# rgbw2.net
KiCad netlist of a schematic drawn in EAGLE
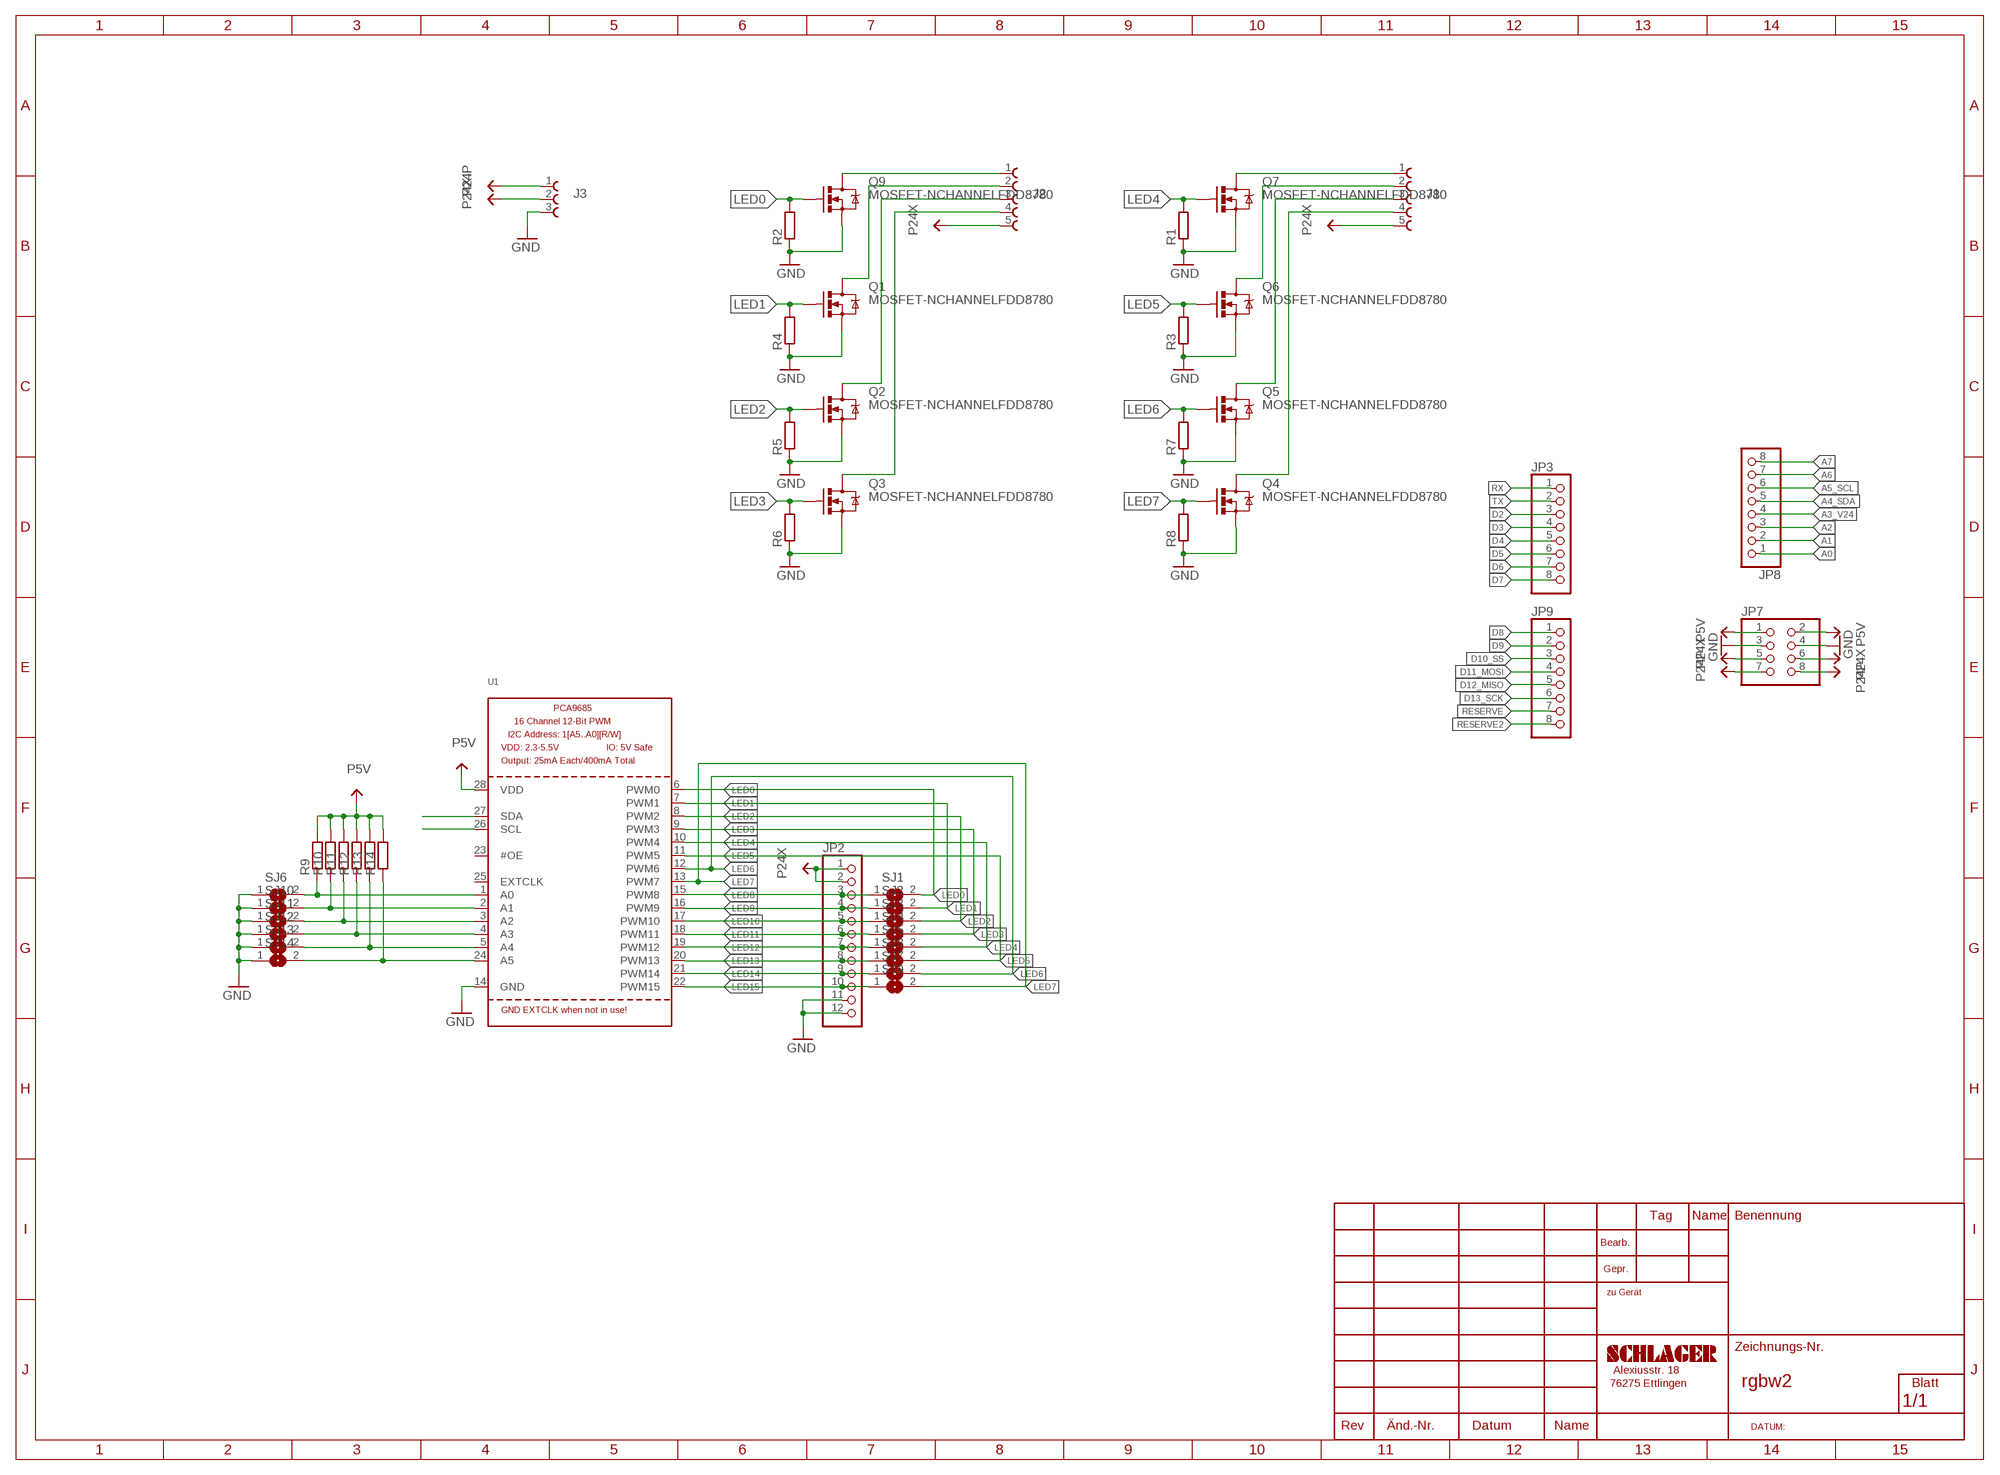
[diagram p0: schematic, sheet 1]

(export (version "E")
  (design (tool "Eeschema 10.0.6"))
  (components
    (comp (ref "J1")
      (value "691322310005")
      (footprint "eagle-import:691322310005")
      (libsource (lib "eagle-import") (part "691322310005"))
    )
    (comp (ref "J2")
      (value "691322310005")
      (footprint "eagle-import:691322310005")
      (libsource (lib "eagle-import") (part "691322310005"))
    )
    (comp (ref "J3")
      (value "691313510003")
      (footprint "eagle-import:691313510003")
      (libsource (lib "eagle-import") (part "691313510003"))
    )
    (comp (ref "JP2")
      (value "PINHD-1X12")
      (footprint "eagle-import:1X12")
      (libsource (lib "eagle-import") (part "PINHD-1X12"))
    )
    (comp (ref "JP3")
      (value "PINHD-1X8")
      (footprint "eagle-import:1X08")
      (libsource (lib "eagle-import") (part "PINHD-1X8"))
    )
    (comp (ref "JP7")
      (value "PINHD-2X4")
      (footprint "eagle-import:2X04")
      (libsource (lib "eagle-import") (part "PINHD-2X4"))
    )
    (comp (ref "JP8")
      (value "PINHD-1X8")
      (footprint "eagle-import:1X08")
      (libsource (lib "eagle-import") (part "PINHD-1X8"))
    )
    (comp (ref "JP9")
      (value "PINHD-1X8")
      (footprint "eagle-import:1X08")
      (libsource (lib "eagle-import") (part "PINHD-1X8"))
    )
    (comp (ref "Q1")
      (value "MOSFET-NCHANNELFDD8780")
      (footprint "eagle-import:DPAK")
      (libsource (lib "eagle-import") (part "MOSFET-NCHANNELFDD8780"))
    )
    (comp (ref "Q2")
      (value "MOSFET-NCHANNELFDD8780")
      (footprint "eagle-import:DPAK")
      (libsource (lib "eagle-import") (part "MOSFET-NCHANNELFDD8780"))
    )
    (comp (ref "Q3")
      (value "MOSFET-NCHANNELFDD8780")
      (footprint "eagle-import:DPAK")
      (libsource (lib "eagle-import") (part "MOSFET-NCHANNELFDD8780"))
    )
    (comp (ref "Q4")
      (value "MOSFET-NCHANNELFDD8780")
      (footprint "eagle-import:DPAK")
      (libsource (lib "eagle-import") (part "MOSFET-NCHANNELFDD8780"))
    )
    (comp (ref "Q5")
      (value "MOSFET-NCHANNELFDD8780")
      (footprint "eagle-import:DPAK")
      (libsource (lib "eagle-import") (part "MOSFET-NCHANNELFDD8780"))
    )
    (comp (ref "Q6")
      (value "MOSFET-NCHANNELFDD8780")
      (footprint "eagle-import:DPAK")
      (libsource (lib "eagle-import") (part "MOSFET-NCHANNELFDD8780"))
    )
    (comp (ref "Q7")
      (value "MOSFET-NCHANNELFDD8780")
      (footprint "eagle-import:DPAK")
      (libsource (lib "eagle-import") (part "MOSFET-NCHANNELFDD8780"))
    )
    (comp (ref "Q9")
      (value "MOSFET-NCHANNELFDD8780")
      (footprint "eagle-import:DPAK")
      (libsource (lib "eagle-import") (part "MOSFET-NCHANNELFDD8780"))
    )
    (comp (ref "R1")
      (value "R-EU_R0805")
      (footprint "eagle-import:R0805")
      (libsource (lib "eagle-import") (part "R-EU_R0805"))
    )
    (comp (ref "R2")
      (value "R-EU_R0805")
      (footprint "eagle-import:R0805")
      (libsource (lib "eagle-import") (part "R-EU_R0805"))
    )
    (comp (ref "R3")
      (value "R-EU_R0805")
      (footprint "eagle-import:R0805")
      (libsource (lib "eagle-import") (part "R-EU_R0805"))
    )
    (comp (ref "R4")
      (value "R-EU_R0805")
      (footprint "eagle-import:R0805")
      (libsource (lib "eagle-import") (part "R-EU_R0805"))
    )
    (comp (ref "R5")
      (value "R-EU_R0805")
      (footprint "eagle-import:R0805")
      (libsource (lib "eagle-import") (part "R-EU_R0805"))
    )
    (comp (ref "R6")
      (value "R-EU_R0805")
      (footprint "eagle-import:R0805")
      (libsource (lib "eagle-import") (part "R-EU_R0805"))
    )
    (comp (ref "R7")
      (value "R-EU_R0805")
      (footprint "eagle-import:R0805")
      (libsource (lib "eagle-import") (part "R-EU_R0805"))
    )
    (comp (ref "R8")
      (value "R-EU_R0805")
      (footprint "eagle-import:R0805")
      (libsource (lib "eagle-import") (part "R-EU_R0805"))
    )
    (comp (ref "R9")
      (value "R-EU_R0805")
      (footprint "eagle-import:R0805")
      (libsource (lib "eagle-import") (part "R-EU_R0805"))
    )
    (comp (ref "R10")
      (value "R-EU_R0805")
      (footprint "eagle-import:R0805")
      (libsource (lib "eagle-import") (part "R-EU_R0805"))
    )
    (comp (ref "R11")
      (value "R-EU_R0805")
      (footprint "eagle-import:R0805")
      (libsource (lib "eagle-import") (part "R-EU_R0805"))
    )
    (comp (ref "R12")
      (value "R-EU_R0805")
      (footprint "eagle-import:R0805")
      (libsource (lib "eagle-import") (part "R-EU_R0805"))
    )
    (comp (ref "R13")
      (value "R-EU_R0805")
      (footprint "eagle-import:R0805")
      (libsource (lib "eagle-import") (part "R-EU_R0805"))
    )
    (comp (ref "R14")
      (value "R-EU_R0805")
      (footprint "eagle-import:R0805")
      (libsource (lib "eagle-import") (part "R-EU_R0805"))
    )
    (comp (ref "SJ1")
      (value "SJN")
      (footprint "eagle-import:SJ")
      (libsource (lib "eagle-import") (part "SJN"))
    )
    (comp (ref "SJ2")
      (value "SJN")
      (footprint "eagle-import:SJ")
      (libsource (lib "eagle-import") (part "SJN"))
    )
    (comp (ref "SJ3")
      (value "SJN")
      (footprint "eagle-import:SJ")
      (libsource (lib "eagle-import") (part "SJN"))
    )
    (comp (ref "SJ4")
      (value "SJN")
      (footprint "eagle-import:SJ")
      (libsource (lib "eagle-import") (part "SJN"))
    )
    (comp (ref "SJ5")
      (value "SJN")
      (footprint "eagle-import:SJ")
      (libsource (lib "eagle-import") (part "SJN"))
    )
    (comp (ref "SJ6")
      (value "SJN")
      (footprint "eagle-import:SJ")
      (libsource (lib "eagle-import") (part "SJN"))
    )
    (comp (ref "SJ7")
      (value "SJN")
      (footprint "eagle-import:SJ")
      (libsource (lib "eagle-import") (part "SJN"))
    )
    (comp (ref "SJ8")
      (value "SJN")
      (footprint "eagle-import:SJ")
      (libsource (lib "eagle-import") (part "SJN"))
    )
    (comp (ref "SJ9")
      (value "SJN")
      (footprint "eagle-import:SJ")
      (libsource (lib "eagle-import") (part "SJN"))
    )
    (comp (ref "SJ10")
      (value "SJN")
      (footprint "eagle-import:SJ")
      (libsource (lib "eagle-import") (part "SJN"))
    )
    (comp (ref "SJ11")
      (value "SJN")
      (footprint "eagle-import:SJ")
      (libsource (lib "eagle-import") (part "SJN"))
    )
    (comp (ref "SJ12")
      (value "SJN")
      (footprint "eagle-import:SJ")
      (libsource (lib "eagle-import") (part "SJN"))
    )
    (comp (ref "SJ13")
      (value "SJN")
      (footprint "eagle-import:SJ")
      (libsource (lib "eagle-import") (part "SJN"))
    )
    (comp (ref "SJ14")
      (value "SJN")
      (footprint "eagle-import:SJ")
      (libsource (lib "eagle-import") (part "SJN"))
    )
    (comp (ref "U1")
      (value "PCA9685")
      (footprint "eagle-import:TSSOP28")
      (libsource (lib "eagle-import") (part "PCA9685"))
    )
  )
  (nets
    (net (code "1") (name "A0") (class "Default")
      (node (ref "JP8") (pin "1") (pinfunction "1_1") (pintype "passive"))
    )
    (net (code "2") (name "A1") (class "Default")
      (node (ref "JP8") (pin "2") (pinfunction "2_2") (pintype "passive"))
    )
    (net (code "3") (name "A2") (class "Default")
      (node (ref "JP8") (pin "3") (pinfunction "3_3") (pintype "passive"))
    )
    (net (code "4") (name "A3_V24") (class "Default")
      (node (ref "JP8") (pin "4") (pinfunction "4_4") (pintype "passive"))
    )
    (net (code "5") (name "A4_SDA") (class "Default")
      (node (ref "JP8") (pin "5") (pinfunction "5_5") (pintype "passive"))
      (node (ref "U1") (pin "27") (pinfunction "SDA_27") (pintype "bidirectional"))
    )
    (net (code "6") (name "A5_SCL") (class "Default")
      (node (ref "JP8") (pin "6") (pinfunction "6_6") (pintype "passive"))
      (node (ref "U1") (pin "26") (pinfunction "SCL_26") (pintype "bidirectional"))
    )
    (net (code "7") (name "A6") (class "Default")
      (node (ref "JP8") (pin "7") (pinfunction "7_7") (pintype "passive"))
    )
    (net (code "8") (name "A7") (class "Default")
      (node (ref "JP8") (pin "8") (pinfunction "8_8") (pintype "passive"))
    )
    (net (code "9") (name "D2") (class "Default")
      (node (ref "JP3") (pin "3") (pinfunction "3_3") (pintype "passive"))
    )
    (net (code "10") (name "D3") (class "Default")
      (node (ref "JP3") (pin "4") (pinfunction "4_4") (pintype "passive"))
    )
    (net (code "11") (name "D4") (class "Default")
      (node (ref "JP3") (pin "5") (pinfunction "5_5") (pintype "passive"))
    )
    (net (code "12") (name "D5") (class "Default")
      (node (ref "JP3") (pin "6") (pinfunction "6_6") (pintype "passive"))
    )
    (net (code "13") (name "D6") (class "Default")
      (node (ref "JP3") (pin "7") (pinfunction "7_7") (pintype "passive"))
    )
    (net (code "14") (name "D7") (class "Default")
      (node (ref "JP3") (pin "8") (pinfunction "8_8") (pintype "passive"))
    )
    (net (code "15") (name "D8") (class "Default")
      (node (ref "JP9") (pin "1") (pinfunction "1_1") (pintype "passive"))
    )
    (net (code "16") (name "D9") (class "Default")
      (node (ref "JP9") (pin "2") (pinfunction "2_2") (pintype "passive"))
    )
    (net (code "17") (name "D10_SS") (class "Default")
      (node (ref "JP9") (pin "3") (pinfunction "3_3") (pintype "passive"))
    )
    (net (code "18") (name "D11_MOSI") (class "Default")
      (node (ref "JP9") (pin "4") (pinfunction "4_4") (pintype "passive"))
    )
    (net (code "19") (name "D12_MISO") (class "Default")
      (node (ref "JP9") (pin "5") (pinfunction "5_5") (pintype "passive"))
    )
    (net (code "20") (name "D13_SCK") (class "Default")
      (node (ref "JP9") (pin "6") (pinfunction "6_6") (pintype "passive"))
    )
    (net (code "21") (name "GND") (class "Default")
      (node (ref "J3") (pin "3") (pinfunction "3_3") (pintype "passive"))
      (node (ref "JP2") (pin "11") (pinfunction "11_11") (pintype "passive"))
      (node (ref "JP2") (pin "12") (pinfunction "12_12") (pintype "passive"))
      (node (ref "JP7") (pin "3") (pinfunction "3_3") (pintype "passive"))
      (node (ref "JP7") (pin "4") (pinfunction "4_4") (pintype "passive"))
      (node (ref "Q1") (pin "3") (pinfunction "S_3") (pintype "passive"))
      (node (ref "Q2") (pin "3") (pinfunction "S_3") (pintype "passive"))
      (node (ref "Q3") (pin "3") (pinfunction "S_3") (pintype "passive"))
      (node (ref "Q4") (pin "3") (pinfunction "S_3") (pintype "passive"))
      (node (ref "Q5") (pin "3") (pinfunction "S_3") (pintype "passive"))
      (node (ref "Q6") (pin "3") (pinfunction "S_3") (pintype "passive"))
      (node (ref "Q7") (pin "3") (pinfunction "S_3") (pintype "passive"))
      (node (ref "Q9") (pin "3") (pinfunction "S_3") (pintype "passive"))
      (node (ref "R1") (pin "1") (pinfunction "1_1") (pintype "passive"))
      (node (ref "R2") (pin "1") (pinfunction "1_1") (pintype "passive"))
      (node (ref "R3") (pin "1") (pinfunction "1_1") (pintype "passive"))
      (node (ref "R4") (pin "1") (pinfunction "1_1") (pintype "passive"))
      (node (ref "R5") (pin "1") (pinfunction "1_1") (pintype "passive"))
      (node (ref "R6") (pin "1") (pinfunction "1_1") (pintype "passive"))
      (node (ref "R7") (pin "1") (pinfunction "1_1") (pintype "passive"))
      (node (ref "R8") (pin "1") (pinfunction "1_1") (pintype "passive"))
      (node (ref "SJ10") (pin "1") (pinfunction "1_1") (pintype "passive"))
      (node (ref "SJ11") (pin "1") (pinfunction "1_1") (pintype "passive"))
      (node (ref "SJ12") (pin "1") (pinfunction "1_1") (pintype "passive"))
      (node (ref "SJ13") (pin "1") (pinfunction "1_1") (pintype "passive"))
      (node (ref "SJ14") (pin "1") (pinfunction "1_1") (pintype "passive"))
      (node (ref "SJ6") (pin "1") (pinfunction "1_1") (pintype "passive"))
      (node (ref "U1") (pin "14") (pinfunction "GND_14") (pintype "power_in"))
    )
    (net (code "22") (name "LED0") (class "Default")
      (node (ref "Q9") (pin "1") (pinfunction "G_1") (pintype "passive"))
      (node (ref "R2") (pin "2") (pinfunction "2_2") (pintype "passive"))
      (node (ref "SJ1") (pin "2") (pinfunction "2_2") (pintype "passive"))
      (node (ref "U1") (pin "6") (pinfunction "PWM0_6") (pintype "output"))
    )
    (net (code "23") (name "LED1") (class "Default")
      (node (ref "Q1") (pin "1") (pinfunction "G_1") (pintype "passive"))
      (node (ref "R4") (pin "2") (pinfunction "2_2") (pintype "passive"))
      (node (ref "SJ2") (pin "2") (pinfunction "2_2") (pintype "passive"))
      (node (ref "U1") (pin "7") (pinfunction "PWM1_7") (pintype "output"))
    )
    (net (code "24") (name "LED2") (class "Default")
      (node (ref "Q2") (pin "1") (pinfunction "G_1") (pintype "passive"))
      (node (ref "R5") (pin "2") (pinfunction "2_2") (pintype "passive"))
      (node (ref "SJ3") (pin "2") (pinfunction "2_2") (pintype "passive"))
      (node (ref "U1") (pin "8") (pinfunction "PWM2_8") (pintype "output"))
    )
    (net (code "25") (name "LED3") (class "Default")
      (node (ref "Q3") (pin "1") (pinfunction "G_1") (pintype "passive"))
      (node (ref "R6") (pin "2") (pinfunction "2_2") (pintype "passive"))
      (node (ref "SJ4") (pin "2") (pinfunction "2_2") (pintype "passive"))
      (node (ref "U1") (pin "9") (pinfunction "PWM3_9") (pintype "output"))
    )
    (net (code "26") (name "LED4") (class "Default")
      (node (ref "Q7") (pin "1") (pinfunction "G_1") (pintype "passive"))
      (node (ref "R1") (pin "2") (pinfunction "2_2") (pintype "passive"))
      (node (ref "SJ5") (pin "2") (pinfunction "2_2") (pintype "passive"))
      (node (ref "U1") (pin "10") (pinfunction "PWM4_10") (pintype "output"))
    )
    (net (code "27") (name "LED5") (class "Default")
      (node (ref "Q6") (pin "1") (pinfunction "G_1") (pintype "passive"))
      (node (ref "R3") (pin "2") (pinfunction "2_2") (pintype "passive"))
      (node (ref "SJ8") (pin "2") (pinfunction "2_2") (pintype "passive"))
      (node (ref "U1") (pin "11") (pinfunction "PWM5_11") (pintype "output"))
    )
    (net (code "28") (name "LED6") (class "Default")
      (node (ref "Q5") (pin "1") (pinfunction "G_1") (pintype "passive"))
      (node (ref "R7") (pin "2") (pinfunction "2_2") (pintype "passive"))
      (node (ref "SJ7") (pin "2") (pinfunction "2_2") (pintype "passive"))
      (node (ref "U1") (pin "12") (pinfunction "PWM6_12") (pintype "output"))
    )
    (net (code "29") (name "LED7") (class "Default")
      (node (ref "Q4") (pin "1") (pinfunction "G_1") (pintype "passive"))
      (node (ref "R8") (pin "2") (pinfunction "2_2") (pintype "passive"))
      (node (ref "SJ9") (pin "2") (pinfunction "2_2") (pintype "passive"))
      (node (ref "U1") (pin "13") (pinfunction "PWM7_13") (pintype "output"))
    )
    (net (code "30") (name "LED8") (class "Default")
      (node (ref "JP2") (pin "3") (pinfunction "3_3") (pintype "passive"))
      (node (ref "SJ1") (pin "1") (pinfunction "1_1") (pintype "passive"))
      (node (ref "U1") (pin "15") (pinfunction "PWM8_15") (pintype "output"))
    )
    (net (code "31") (name "LED9") (class "Default")
      (node (ref "JP2") (pin "4") (pinfunction "4_4") (pintype "passive"))
      (node (ref "SJ2") (pin "1") (pinfunction "1_1") (pintype "passive"))
      (node (ref "U1") (pin "16") (pinfunction "PWM9_16") (pintype "output"))
    )
    (net (code "32") (name "LED10") (class "Default")
      (node (ref "JP2") (pin "5") (pinfunction "5_5") (pintype "passive"))
      (node (ref "SJ3") (pin "1") (pinfunction "1_1") (pintype "passive"))
      (node (ref "U1") (pin "17") (pinfunction "PWM10_17") (pintype "output"))
    )
    (net (code "33") (name "LED11") (class "Default")
      (node (ref "JP2") (pin "6") (pinfunction "6_6") (pintype "passive"))
      (node (ref "SJ4") (pin "1") (pinfunction "1_1") (pintype "passive"))
      (node (ref "U1") (pin "18") (pinfunction "PWM11_18") (pintype "output"))
    )
    (net (code "34") (name "LED12") (class "Default")
      (node (ref "JP2") (pin "7") (pinfunction "7_7") (pintype "passive"))
      (node (ref "SJ5") (pin "1") (pinfunction "1_1") (pintype "passive"))
      (node (ref "U1") (pin "19") (pinfunction "PWM12_19") (pintype "output"))
    )
    (net (code "35") (name "LED13") (class "Default")
      (node (ref "JP2") (pin "8") (pinfunction "8_8") (pintype "passive"))
      (node (ref "SJ8") (pin "1") (pinfunction "1_1") (pintype "passive"))
      (node (ref "U1") (pin "20") (pinfunction "PWM13_20") (pintype "output"))
    )
    (net (code "36") (name "LED14") (class "Default")
      (node (ref "JP2") (pin "9") (pinfunction "9_9") (pintype "passive"))
      (node (ref "SJ7") (pin "1") (pinfunction "1_1") (pintype "passive"))
      (node (ref "U1") (pin "21") (pinfunction "PWM14_21") (pintype "output"))
    )
    (net (code "37") (name "LED15") (class "Default")
      (node (ref "JP2") (pin "10") (pinfunction "10_10") (pintype "passive"))
      (node (ref "SJ9") (pin "1") (pinfunction "1_1") (pintype "passive"))
      (node (ref "U1") (pin "22") (pinfunction "PWM15_22") (pintype "output"))
    )
    (net (code "38") (name "Net-(Q1-D)") (class "Default")
      (node (ref "J2") (pin "2") (pinfunction "2_2") (pintype "passive"))
      (node (ref "Q1") (pin "4") (pinfunction "D_4") (pintype "passive"))
    )
    (net (code "39") (name "Net-(Q2-D)") (class "Default")
      (node (ref "J2") (pin "3") (pinfunction "3_3") (pintype "passive"))
      (node (ref "Q2") (pin "4") (pinfunction "D_4") (pintype "passive"))
    )
    (net (code "40") (name "Net-(Q3-D)") (class "Default")
      (node (ref "J2") (pin "4") (pinfunction "4_4") (pintype "passive"))
      (node (ref "Q3") (pin "4") (pinfunction "D_4") (pintype "passive"))
    )
    (net (code "41") (name "Net-(Q4-D)") (class "Default")
      (node (ref "J1") (pin "4") (pinfunction "4_4") (pintype "passive"))
      (node (ref "Q4") (pin "4") (pinfunction "D_4") (pintype "passive"))
    )
    (net (code "42") (name "Net-(Q5-D)") (class "Default")
      (node (ref "J1") (pin "3") (pinfunction "3_3") (pintype "passive"))
      (node (ref "Q5") (pin "4") (pinfunction "D_4") (pintype "passive"))
    )
    (net (code "43") (name "Net-(Q6-D)") (class "Default")
      (node (ref "J1") (pin "2") (pinfunction "2_2") (pintype "passive"))
      (node (ref "Q6") (pin "4") (pinfunction "D_4") (pintype "passive"))
    )
    (net (code "44") (name "Net-(Q7-D)") (class "Default")
      (node (ref "J1") (pin "1") (pinfunction "1_1") (pintype "passive"))
      (node (ref "Q7") (pin "4") (pinfunction "D_4") (pintype "passive"))
    )
    (net (code "45") (name "Net-(Q9-D)") (class "Default")
      (node (ref "J2") (pin "1") (pinfunction "1_1") (pintype "passive"))
      (node (ref "Q9") (pin "4") (pinfunction "D_4") (pintype "passive"))
    )
    (net (code "46") (name "Net-(U1-A0)") (class "Default")
      (node (ref "R9") (pin "1") (pinfunction "1_1") (pintype "passive"))
      (node (ref "SJ6") (pin "2") (pinfunction "2_2") (pintype "passive"))
      (node (ref "U1") (pin "1") (pinfunction "A0_1") (pintype "bidirectional"))
    )
    (net (code "47") (name "Net-(U1-A1)") (class "Default")
      (node (ref "R10") (pin "1") (pinfunction "1_1") (pintype "passive"))
      (node (ref "SJ10") (pin "2") (pinfunction "2_2") (pintype "passive"))
      (node (ref "U1") (pin "2") (pinfunction "A1_2") (pintype "bidirectional"))
    )
    (net (code "48") (name "Net-(U1-A2)") (class "Default")
      (node (ref "R11") (pin "1") (pinfunction "1_1") (pintype "passive"))
      (node (ref "SJ11") (pin "2") (pinfunction "2_2") (pintype "passive"))
      (node (ref "U1") (pin "3") (pinfunction "A2_3") (pintype "bidirectional"))
    )
    (net (code "49") (name "Net-(U1-A3)") (class "Default")
      (node (ref "R12") (pin "1") (pinfunction "1_1") (pintype "passive"))
      (node (ref "SJ12") (pin "2") (pinfunction "2_2") (pintype "passive"))
      (node (ref "U1") (pin "4") (pinfunction "A3_4") (pintype "bidirectional"))
    )
    (net (code "50") (name "Net-(U1-A4)") (class "Default")
      (node (ref "R13") (pin "1") (pinfunction "1_1") (pintype "passive"))
      (node (ref "SJ13") (pin "2") (pinfunction "2_2") (pintype "passive"))
      (node (ref "U1") (pin "5") (pinfunction "A4_5") (pintype "bidirectional"))
    )
    (net (code "51") (name "Net-(U1-A5)") (class "Default")
      (node (ref "R14") (pin "1") (pinfunction "1_1") (pintype "passive"))
      (node (ref "SJ14") (pin "2") (pinfunction "2_2") (pintype "passive"))
      (node (ref "U1") (pin "24") (pinfunction "A5_24") (pintype "bidirectional"))
    )
    (net (code "52") (name "P5V") (class "Default")
      (node (ref "JP7") (pin "1") (pinfunction "1_1") (pintype "passive"))
      (node (ref "JP7") (pin "2") (pinfunction "2_2") (pintype "passive"))
      (node (ref "R10") (pin "2") (pinfunction "2_2") (pintype "passive"))
      (node (ref "R11") (pin "2") (pinfunction "2_2") (pintype "passive"))
      (node (ref "R12") (pin "2") (pinfunction "2_2") (pintype "passive"))
      (node (ref "R13") (pin "2") (pinfunction "2_2") (pintype "passive"))
      (node (ref "R14") (pin "2") (pinfunction "2_2") (pintype "passive"))
      (node (ref "R9") (pin "2") (pinfunction "2_2") (pintype "passive"))
      (node (ref "U1") (pin "28") (pinfunction "VDD_28") (pintype "power_in"))
    )
    (net (code "53") (name "P24P") (class "Default")
      (node (ref "J3") (pin "1") (pinfunction "1_1") (pintype "passive"))
      (node (ref "JP7") (pin "7") (pinfunction "7_7") (pintype "passive"))
      (node (ref "JP7") (pin "8") (pinfunction "8_8") (pintype "passive"))
    )
    (net (code "54") (name "P24X") (class "Default")
      (node (ref "J1") (pin "5") (pinfunction "5_5") (pintype "passive"))
      (node (ref "J2") (pin "5") (pinfunction "5_5") (pintype "passive"))
      (node (ref "J3") (pin "2") (pinfunction "2_2") (pintype "passive"))
      (node (ref "JP2") (pin "1") (pinfunction "1_1") (pintype "passive"))
      (node (ref "JP2") (pin "2") (pinfunction "2_2") (pintype "passive"))
      (node (ref "JP7") (pin "5") (pinfunction "5_5") (pintype "passive"))
      (node (ref "JP7") (pin "6") (pinfunction "6_6") (pintype "passive"))
    )
    (net (code "55") (name "RESERVE") (class "Default")
      (node (ref "JP9") (pin "7") (pinfunction "7_7") (pintype "passive"))
    )
    (net (code "56") (name "RESERVE2") (class "Default")
      (node (ref "JP9") (pin "8") (pinfunction "8_8") (pintype "passive"))
    )
    (net (code "57") (name "RX") (class "Default")
      (node (ref "JP3") (pin "1") (pinfunction "1_1") (pintype "passive"))
    )
    (net (code "58") (name "TX") (class "Default")
      (node (ref "JP3") (pin "2") (pinfunction "2_2") (pintype "passive"))
    )
    (net (code "59") (name "unconnected-(U1-#OE-Pad23)") (class "Default")
      (node (ref "U1") (pin "23") (pinfunction "#OE_23") (pintype "input"))
    )
    (net (code "60") (name "unconnected-(U1-EXTCLK-Pad25)") (class "Default")
      (node (ref "U1") (pin "25") (pinfunction "EXTCLK_25") (pintype "input"))
    )
  )
)
